# Uno.net
KiCad netlist of a schematic drawn in EAGLE
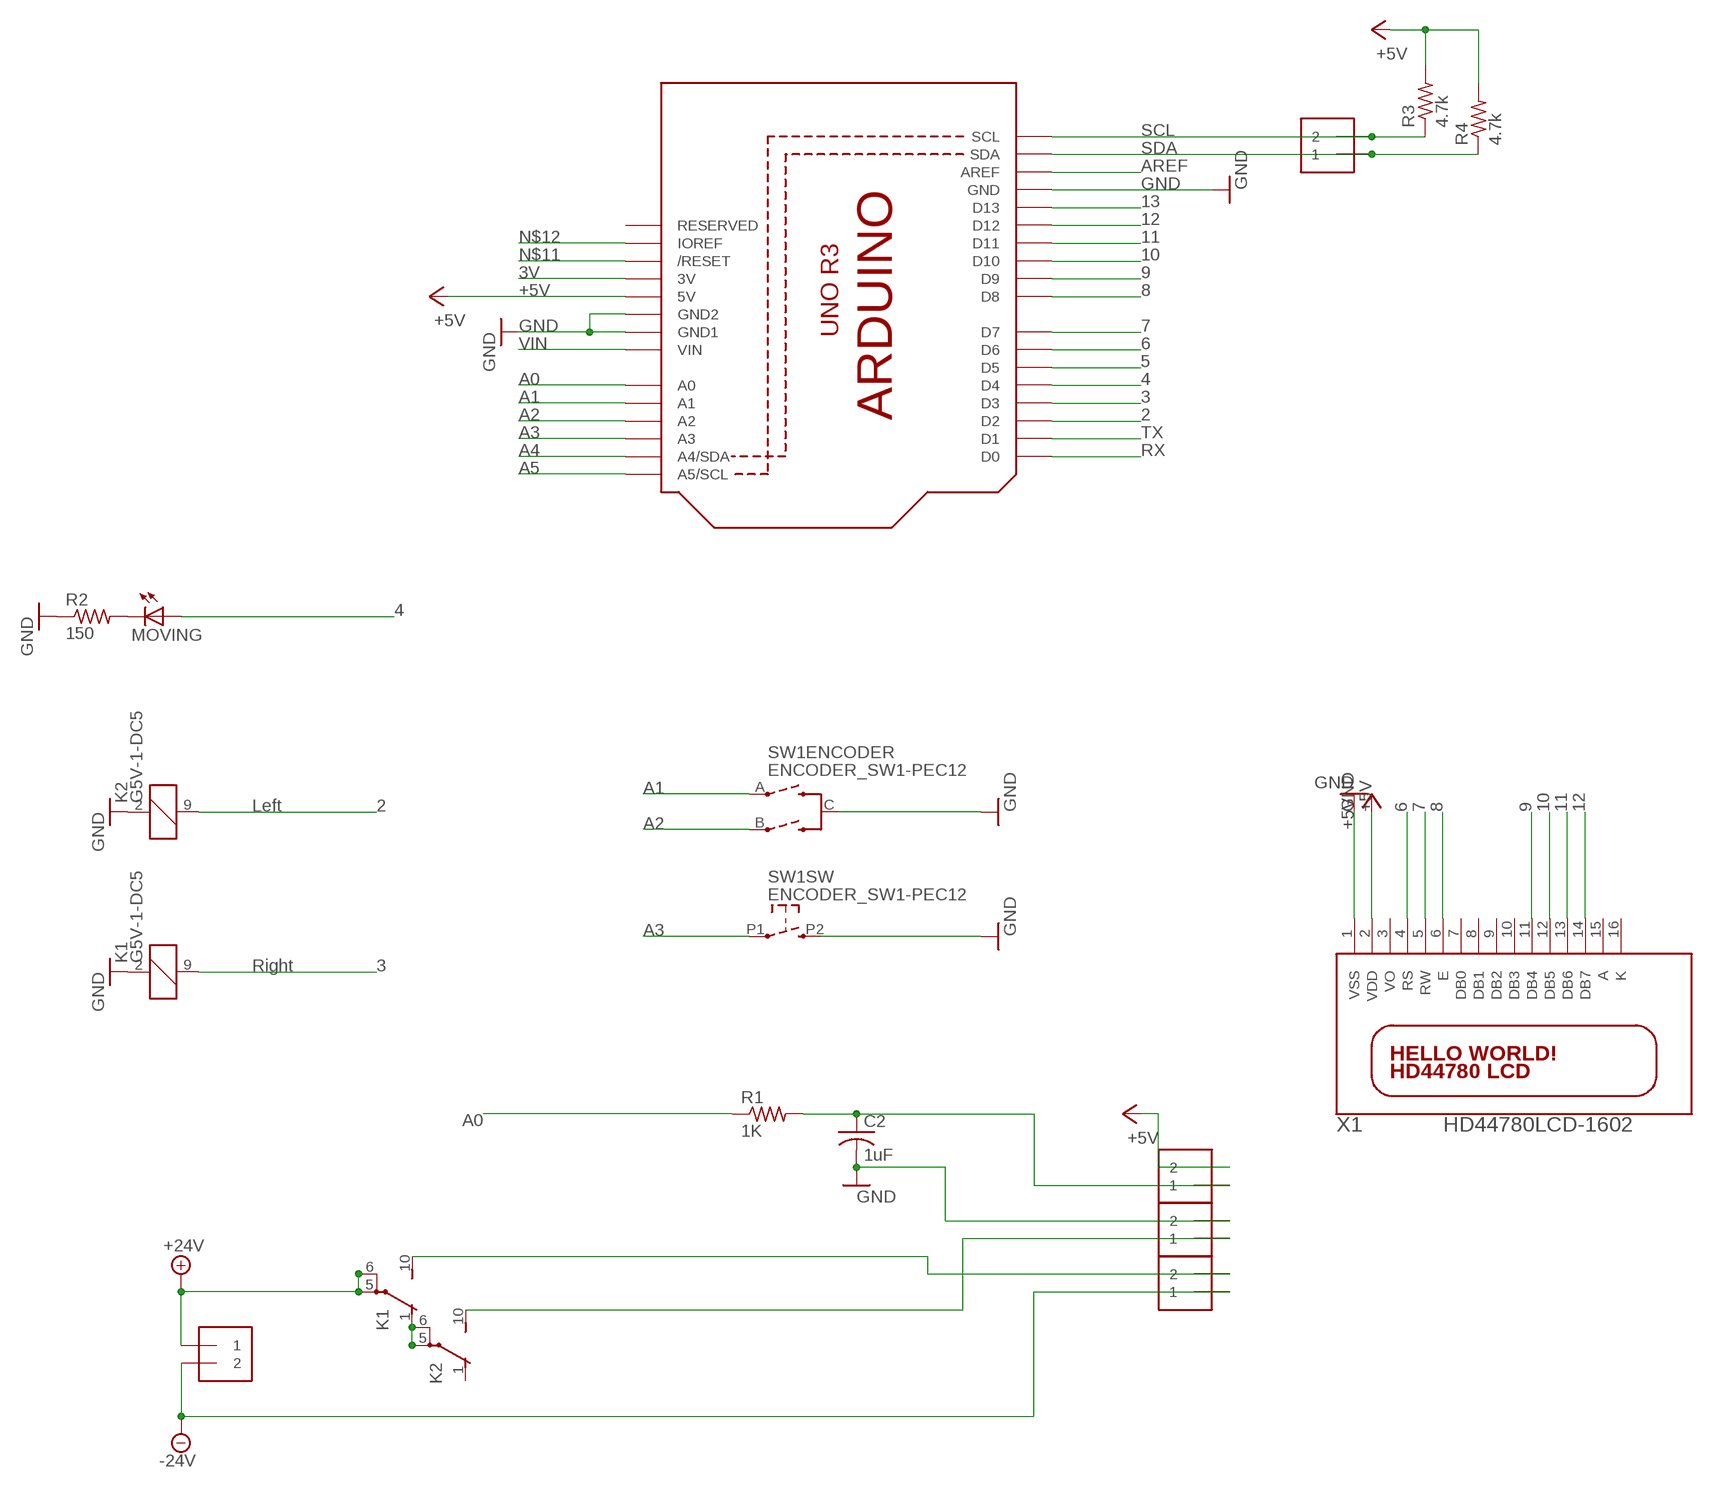
[diagram p0: schematic, sheet 1]

(export (version "E")
  (design (tool "Eeschema 10.0.6"))
  (components
    (comp (ref "C2")
      (value "1uF")
      (footprint "eagle-import:C050-024X044")
      (libsource (lib "eagle-import") (part "C-US050-024X044"))
    )
    (comp (ref "J1")
      (value "1X2-3.5MM")
      (footprint "eagle-import:1X2-3.5MM")
      (libsource (lib "eagle-import") (part "1X2-3.5MM"))
    )
    (comp (ref "J2")
      (value "1X2-3.5MM")
      (footprint "eagle-import:1X2-3.5MM")
      (libsource (lib "eagle-import") (part "1X2-3.5MM"))
    )
    (comp (ref "J3")
      (value "1X2-3.5MM")
      (footprint "eagle-import:1X2-3.5MM")
      (libsource (lib "eagle-import") (part "1X2-3.5MM"))
    )
    (comp (ref "J4")
      (value "1X2-3.5MM")
      (footprint "eagle-import:1X2-3.5MM")
      (libsource (lib "eagle-import") (part "1X2-3.5MM"))
    )
    (comp (ref "J5")
      (value "1X2-3.5MM")
      (footprint "eagle-import:1X2-3.5MM")
      (libsource (lib "eagle-import") (part "1X2-3.5MM"))
    )
    (comp (ref "K1")
      (value "G5V-1-DC5")
      (footprint "eagle-import:G5V1")
      (fields (field (name "MPN") "G5V-1-DC24"))
      (libsource (lib "eagle-import") (part "G5V1"))
    )
    (comp (ref "K2")
      (value "G5V-1-DC5")
      (footprint "eagle-import:G5V1")
      (fields (field (name "MPN") "G5V-1-DC24"))
      (libsource (lib "eagle-import") (part "G5V1"))
    )
    (comp (ref "MOVING")
      (value "LED5MM")
      (footprint "eagle-import:LED5MM")
      (libsource (lib "eagle-import") (part "LED5MM"))
    )
    (comp (ref "R1")
      (value "1K")
      (footprint "eagle-import:0414V")
      (libsource (lib "eagle-import") (part "R-US_0414/5V"))
    )
    (comp (ref "R2")
      (value "150")
      (footprint "eagle-import:0207_5V")
      (libsource (lib "eagle-import") (part "R-US_0207/5V"))
    )
    (comp (ref "R3")
      (value "4.7k")
      (footprint "eagle-import:0207_5V")
      (libsource (lib "eagle-import") (part "R-US_0207/5V"))
    )
    (comp (ref "R4")
      (value "4.7k")
      (footprint "eagle-import:0207_5V")
      (libsource (lib "eagle-import") (part "R-US_0207/5V"))
    )
    (comp (ref "SW1")
      (value "ENCODER_SW1-PEC12")
      (footprint "eagle-import:PEC12_INCREMENTAL_ENCODER")
      (libsource (lib "eagle-import") (part "ENCODER_SW1-PEC12"))
    )
    (comp (ref "U1")
      (value "ARDUINOR3-BPLACE")
      (footprint "eagle-import:ARDUINOR3-BPLACE")
      (libsource (lib "eagle-import") (part "ARDUINOR3-BPLACE"))
    )
    (comp (ref "X1")
      (value "HD44780LCD-1602")
      (footprint "eagle-import:LCD1602")
      (libsource (lib "eagle-import") (part "HD44780LCD-1602"))
    )
  )
  (nets
    (net (code "1") (name "+5V") (class "Default")
      (node (ref "J5") (pin "2") (pinfunction "2_2") (pintype "passive"))
      (node (ref "R3") (pin "2") (pinfunction "2_2") (pintype "passive"))
      (node (ref "R4") (pin "2") (pinfunction "2_2") (pintype "passive"))
      (node (ref "U1") (pin "5V") (pinfunction "5V_5V") (pintype "power_in"))
      (node (ref "X1") (pin "2") (pinfunction "VDD_2") (pintype "power_in"))
    )
    (net (code "2") (name "+24V") (class "Default")
      (node (ref "J2") (pin "1") (pinfunction "1_1") (pintype "passive"))
      (node (ref "K1") (pin "5") (pinfunction "P_5") (pintype "passive"))
      (node (ref "K1") (pin "6") (pinfunction "P_6") (pintype "passive"))
    )
    (net (code "3") (name "-24V") (class "Default")
      (node (ref "J2") (pin "2") (pinfunction "2_2") (pintype "passive"))
      (node (ref "J3") (pin "1") (pinfunction "1_1") (pintype "passive"))
    )
    (net (code "4") (name "/2") (class "Default")
      (node (ref "K2") (pin "9") (pinfunction "2_9") (pintype "passive"))
      (node (ref "U1") (pin "D2") (pinfunction "D2_D2") (pintype "bidirectional"))
    )
    (net (code "5") (name "/3") (class "Default")
      (node (ref "K1") (pin "9") (pinfunction "2_9") (pintype "passive"))
      (node (ref "U1") (pin "D3") (pinfunction "D3_D3") (pintype "bidirectional"))
    )
    (net (code "6") (name "/3V") (class "Default")
      (node (ref "U1") (pin "3V") (pinfunction "3V_3V") (pintype "power_in"))
    )
    (net (code "7") (name "/4") (class "Default")
      (node (ref "MOVING") (pin "A") (pinfunction "A_A") (pintype "passive"))
      (node (ref "U1") (pin "D4") (pinfunction "D4_D4") (pintype "bidirectional"))
    )
    (net (code "8") (name "/5") (class "Default")
      (node (ref "U1") (pin "D5") (pinfunction "D5_D5") (pintype "bidirectional"))
    )
    (net (code "9") (name "/6") (class "Default")
      (node (ref "U1") (pin "D6") (pinfunction "D6_D6") (pintype "bidirectional"))
      (node (ref "X1") (pin "4") (pinfunction "RS_4") (pintype "input"))
    )
    (net (code "10") (name "/7") (class "Default")
      (node (ref "U1") (pin "D7") (pinfunction "D7_D7") (pintype "bidirectional"))
      (node (ref "X1") (pin "5") (pinfunction "RW_5") (pintype "input"))
    )
    (net (code "11") (name "/8") (class "Default")
      (node (ref "U1") (pin "D8") (pinfunction "D8_D8") (pintype "bidirectional"))
      (node (ref "X1") (pin "6") (pinfunction "E_6") (pintype "input"))
    )
    (net (code "12") (name "/9") (class "Default")
      (node (ref "U1") (pin "D9") (pinfunction "D9_D9") (pintype "bidirectional"))
      (node (ref "X1") (pin "11") (pinfunction "DB4_11") (pintype "bidirectional"))
    )
    (net (code "13") (name "/10") (class "Default")
      (node (ref "U1") (pin "D10") (pinfunction "D10_D10") (pintype "bidirectional"))
      (node (ref "X1") (pin "12") (pinfunction "DB5_12") (pintype "bidirectional"))
    )
    (net (code "14") (name "/11") (class "Default")
      (node (ref "U1") (pin "D11") (pinfunction "D11_D11") (pintype "bidirectional"))
      (node (ref "X1") (pin "13") (pinfunction "DB6_13") (pintype "bidirectional"))
    )
    (net (code "15") (name "/12") (class "Default")
      (node (ref "U1") (pin "D12") (pinfunction "D12_D12") (pintype "bidirectional"))
      (node (ref "X1") (pin "14") (pinfunction "DB7_14") (pintype "bidirectional"))
    )
    (net (code "16") (name "/13") (class "Default")
      (node (ref "U1") (pin "D13") (pinfunction "D13_D13") (pintype "bidirectional"))
    )
    (net (code "17") (name "/A0") (class "Default")
      (node (ref "R1") (pin "1") (pinfunction "1_1") (pintype "passive"))
      (node (ref "U1") (pin "A0") (pinfunction "A0_A0") (pintype "bidirectional"))
    )
    (net (code "18") (name "/A1") (class "Default")
      (node (ref "SW1") (pin "A") (pinfunction "A_A") (pintype "passive"))
      (node (ref "U1") (pin "A1") (pinfunction "A1_A1") (pintype "bidirectional"))
    )
    (net (code "19") (name "/A2") (class "Default")
      (node (ref "SW1") (pin "B") (pinfunction "B_B") (pintype "passive"))
      (node (ref "U1") (pin "A2") (pinfunction "A2_A2") (pintype "bidirectional"))
    )
    (net (code "20") (name "/A3") (class "Default")
      (node (ref "SW1") (pin "P1") (pinfunction "1_P1") (pintype "passive"))
      (node (ref "U1") (pin "A3") (pinfunction "A3_A3") (pintype "bidirectional"))
    )
    (net (code "21") (name "/A4") (class "Default")
      (node (ref "U1") (pin "A4") (pinfunction "A4/SDA_A4") (pintype "bidirectional"))
    )
    (net (code "22") (name "/A5") (class "Default")
      (node (ref "U1") (pin "A5") (pinfunction "A5/SCL_A5") (pintype "bidirectional"))
    )
    (net (code "23") (name "/AREF") (class "Default")
      (node (ref "U1") (pin "AREF") (pinfunction "AREF_AREF") (pintype "bidirectional"))
    )
    (net (code "24") (name "/N$11") (class "Default")
      (node (ref "U1") (pin "RESET") (pinfunction "/RESET_RESET") (pintype "bidirectional"))
    )
    (net (code "25") (name "/N$12") (class "Default")
      (node (ref "U1") (pin "IOREF") (pinfunction "IOREF_IOREF") (pintype "output"))
    )
    (net (code "26") (name "/RX") (class "Default")
      (node (ref "U1") (pin "D0") (pinfunction "D0_D0") (pintype "bidirectional"))
    )
    (net (code "27") (name "/SCL") (class "Default")
      (node (ref "J1") (pin "2") (pinfunction "2_2") (pintype "passive"))
      (node (ref "R3") (pin "1") (pinfunction "1_1") (pintype "passive"))
      (node (ref "U1") (pin "SCL") (pinfunction "SCL_SCL") (pintype "bidirectional"))
    )
    (net (code "28") (name "/SDA") (class "Default")
      (node (ref "J1") (pin "1") (pinfunction "1_1") (pintype "passive"))
      (node (ref "R4") (pin "1") (pinfunction "1_1") (pintype "passive"))
      (node (ref "U1") (pin "SDA") (pinfunction "SDA_SDA") (pintype "bidirectional"))
    )
    (net (code "29") (name "/TX") (class "Default")
      (node (ref "U1") (pin "D1") (pinfunction "D1_D1") (pintype "bidirectional"))
    )
    (net (code "30") (name "/VIN") (class "Default")
      (node (ref "U1") (pin "VIN") (pinfunction "VIN_VIN") (pintype "power_in"))
    )
    (net (code "31") (name "GND") (class "Default")
      (node (ref "C2") (pin "2") (pinfunction "2_2") (pintype "passive"))
      (node (ref "J4") (pin "2") (pinfunction "2_2") (pintype "passive"))
      (node (ref "K1") (pin "2") (pinfunction "1_2") (pintype "passive"))
      (node (ref "K2") (pin "2") (pinfunction "1_2") (pintype "passive"))
      (node (ref "R2") (pin "1") (pinfunction "1_1") (pintype "passive"))
      (node (ref "SW1") (pin "C") (pinfunction "C_C") (pintype "passive"))
      (node (ref "SW1") (pin "P2") (pinfunction "2_P2") (pintype "passive"))
      (node (ref "U1") (pin "GND") (pinfunction "GND_GND") (pintype "power_in"))
      (node (ref "U1") (pin "GND1") (pinfunction "GND1_GND1") (pintype "power_in"))
      (node (ref "U1") (pin "GND2") (pinfunction "GND2_GND2") (pintype "power_in"))
      (node (ref "X1") (pin "1") (pinfunction "VSS_1") (pintype "power_in"))
    )
    (net (code "32") (name "Net-(C2-Pad1)") (class "Default")
      (node (ref "C2") (pin "1") (pinfunction "1_1") (pintype "passive"))
      (node (ref "J5") (pin "1") (pinfunction "1_1") (pintype "passive"))
      (node (ref "R1") (pin "2") (pinfunction "2_2") (pintype "passive"))
    )
    (net (code "33") (name "Net-(K1B-O)") (class "Default")
      (node (ref "K1") (pin "1") (pinfunction "O_1") (pintype "passive"))
      (node (ref "K2") (pin "5") (pinfunction "P_5") (pintype "passive"))
      (node (ref "K2") (pin "6") (pinfunction "P_6") (pintype "passive"))
    )
    (net (code "34") (name "Net-(K1B-S)") (class "Default")
      (node (ref "J3") (pin "2") (pinfunction "2_2") (pintype "passive"))
      (node (ref "K1") (pin "10") (pinfunction "S_10") (pintype "passive"))
    )
    (net (code "35") (name "Net-(K2B-S)") (class "Default")
      (node (ref "J4") (pin "1") (pinfunction "1_1") (pintype "passive"))
      (node (ref "K2") (pin "10") (pinfunction "S_10") (pintype "passive"))
    )
    (net (code "36") (name "Net-(MOVING-C)") (class "Default")
      (node (ref "MOVING") (pin "K") (pinfunction "C_K") (pintype "passive"))
      (node (ref "R2") (pin "2") (pinfunction "2_2") (pintype "passive"))
    )
    (net (code "37") (name "unconnected-(K2B-O-Pad1)") (class "Default")
      (node (ref "K2") (pin "1") (pinfunction "O_1") (pintype "passive"))
    )
    (net (code "38") (name "unconnected-(U1-PadRESERVED)") (class "Default")
      (node (ref "U1") (pin "RESERVED") (pinfunction "RESERVED_RESERVED") (pintype "no_connect"))
    )
    (net (code "39") (name "unconnected-(X1-A-Pad15)") (class "Default")
      (node (ref "X1") (pin "15") (pinfunction "A_15") (pintype "input"))
    )
    (net (code "40") (name "unconnected-(X1-DB0-Pad7)") (class "Default")
      (node (ref "X1") (pin "7") (pinfunction "DB0_7") (pintype "bidirectional"))
    )
    (net (code "41") (name "unconnected-(X1-DB1-Pad8)") (class "Default")
      (node (ref "X1") (pin "8") (pinfunction "DB1_8") (pintype "bidirectional"))
    )
    (net (code "42") (name "unconnected-(X1-DB2-Pad9)") (class "Default")
      (node (ref "X1") (pin "9") (pinfunction "DB2_9") (pintype "bidirectional"))
    )
    (net (code "43") (name "unconnected-(X1-DB3-Pad10)") (class "Default")
      (node (ref "X1") (pin "10") (pinfunction "DB3_10") (pintype "bidirectional"))
    )
    (net (code "44") (name "unconnected-(X1-K-Pad16)") (class "Default")
      (node (ref "X1") (pin "16") (pinfunction "K_16") (pintype "input"))
    )
    (net (code "45") (name "unconnected-(X1-VO-Pad3)") (class "Default")
      (node (ref "X1") (pin "3") (pinfunction "VO_3") (pintype "input"))
    )
  )
)
